# Smart_Tiestu_v4.net
KiCad netlist of a schematic drawn in EasyEDA
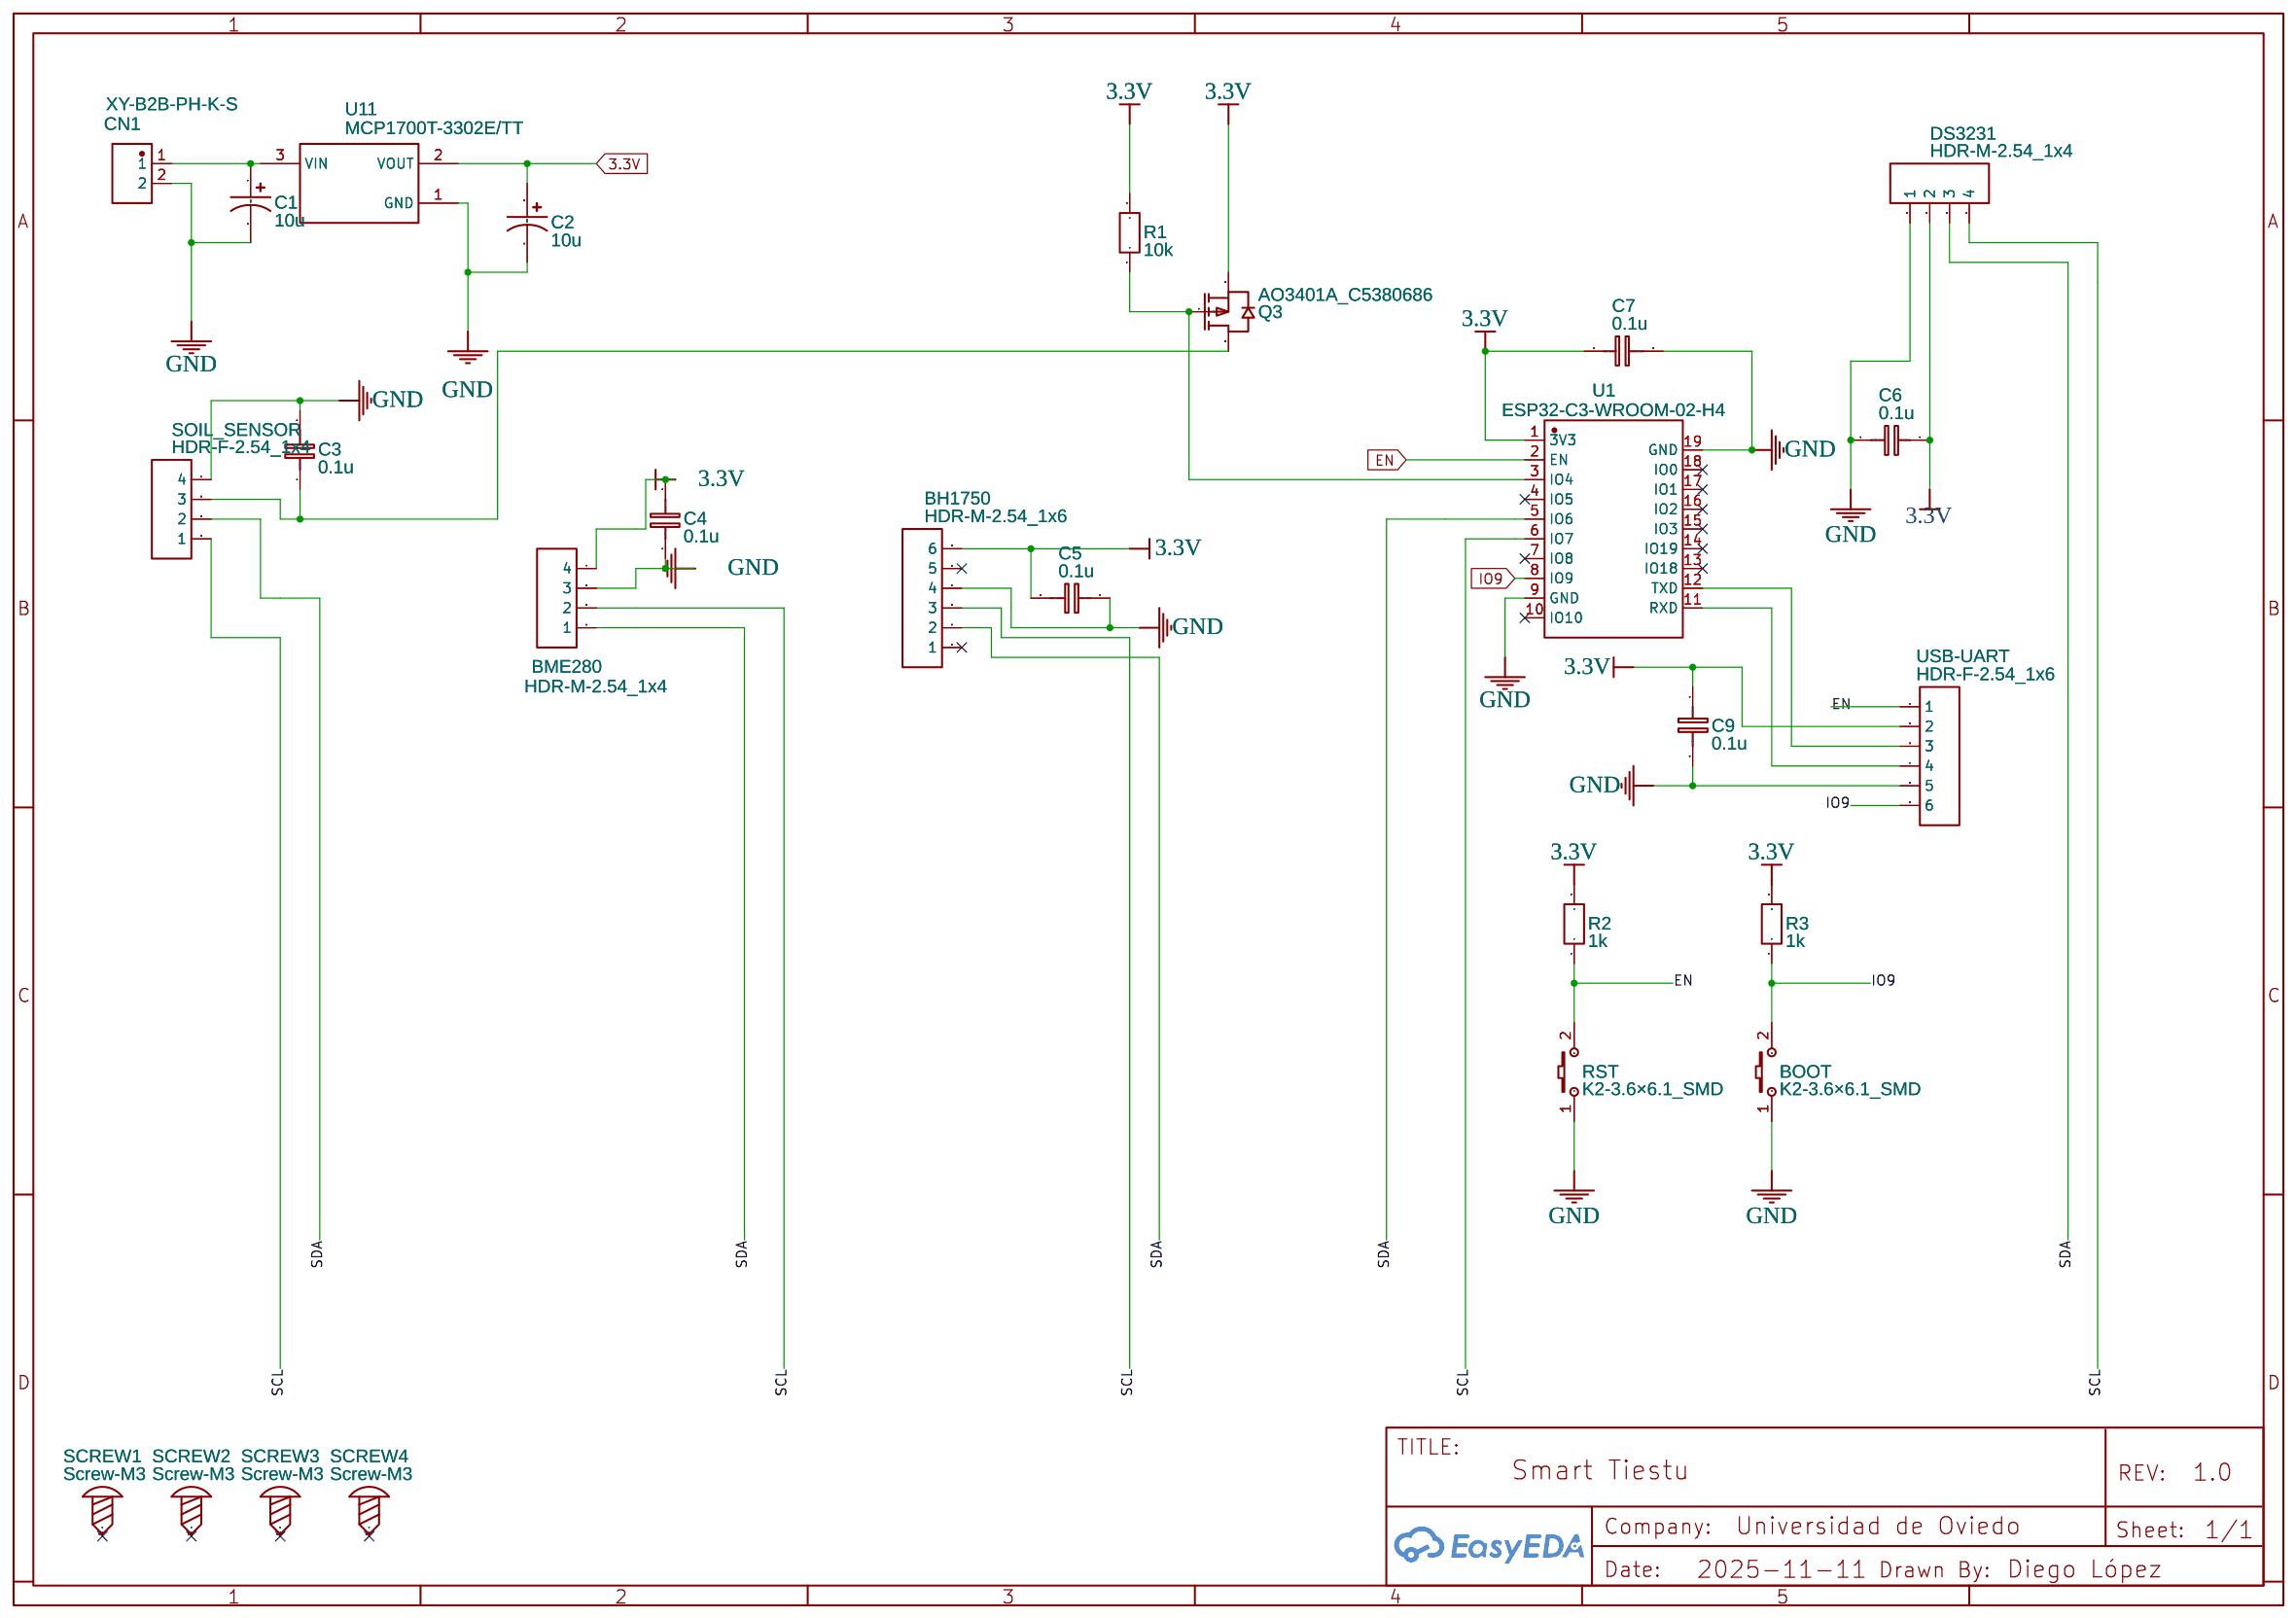
[diagram p0: schematic sheet]

(export (version "E")
  (design (tool "Eeschema 10.0.6"))
  (components
    (comp (ref "BH1750") (value "HDR-M-2.54_1x6") (libsource (lib "") (part "HDR-M-2.54_1x6")))
    (comp (ref "BME280") (value "HDR-M-2.54_1x4") (libsource (lib "") (part "HDR-M-2.54_1x4_1")))
    (comp (ref "BOOT")
      (value "K2-3.6×6.1_SMD")
      (fields (field (name "Manufacturer Part") "K2-1107ST-A4SW-06"))
      (libsource (lib "") (part "K2-3.6×6.1_SMD_1"))
    )
    (comp (ref "C1") (value "10u") (libsource (lib "") (part "C_Tan_SMD_A_US_1")))
    (comp (ref "C2") (value "10u") (libsource (lib "") (part "C_Tan_SMD_A_US")))
    (comp (ref "C3") (value "0.1u") (libsource (lib "") (part "C_0805_EU_1")))
    (comp (ref "C4") (value "0.1u") (libsource (lib "") (part "C_0805_EU_1")))
    (comp (ref "C5") (value "0.1u") (libsource (lib "") (part "C_0805_EU_2")))
    (comp (ref "C6") (value "0.1u") (libsource (lib "") (part "C_0805_EU")))
    (comp (ref "C7") (value "0.1u") (libsource (lib "") (part "C_0805_EU_4")))
    (comp (ref "C9") (value "0.1u") (libsource (lib "") (part "C_0805_EU_3")))
    (comp (ref "CN1")
      (value "XY-B2B-PH-K-S")
      (fields (field (name "Manufacturer") "XYECONN(辛译)"))
      (libsource (lib "") (part "XY-B2B-PH-K-S"))
    )
    (comp (ref "DS3231") (value "HDR-M-2.54_1x4") (libsource (lib "") (part "HDR-M-2.54_1x4")))
    (comp (ref "Q3")
      (value "AO3401A_C5380686")
      (fields (field (name "Manufacturer Part") "AO3401A") (field (name "Manufacturer") "FUXINSEMI(富芯森美)"))
      (libsource (lib "") (part "AO3401A_C5380686"))
    )
    (comp (ref "R1") (value "10k") (libsource (lib "") (part "R_0603_EU")))
    (comp (ref "R2") (value "1k") (libsource (lib "") (part "R_0603_EU")))
    (comp (ref "R3") (value "1k") (libsource (lib "") (part "R_0603_EU")))
    (comp (ref "RST")
      (value "K2-3.6×6.1_SMD")
      (fields (field (name "Manufacturer Part") "K2-1107ST-A4SW-06"))
      (libsource (lib "") (part "K2-3.6×6.1_SMD"))
    )
    (comp (ref "SCREW1") (value "Screw-M3") (libsource (lib "") (part "Screw-M3")))
    (comp (ref "SCREW2") (value "Screw-M3") (libsource (lib "") (part "Screw-M3")))
    (comp (ref "SCREW3") (value "Screw-M3") (libsource (lib "") (part "Screw-M3")))
    (comp (ref "SCREW4") (value "Screw-M3") (libsource (lib "") (part "Screw-M3")))
    (comp (ref "SOIL_SENSOR") (value "HDR-F-2.54_1x4") (libsource (lib "") (part "HDR-F-2.54_1x4")))
    (comp (ref "U1")
      (value "ESP32-C3-WROOM-02-H4")
      (fields (field (name "Manufacturer") "ESPRESSIF(乐鑫)"))
      (libsource (lib "") (part "ESP32-C3-WROOM-02-H4"))
    )
    (comp (ref "U11")
      (value "MCP1700T-3302E/TT")
      (fields (field (name "Manufacturer") "MICROCHIP(美国微芯)"))
      (libsource (lib "") (part "MCP1700T-3302E/TT"))
    )
    (comp (ref "USB-UART") (value "HDR-F-2.54_1x6") (libsource (lib "") (part "HDR-F-2.54_1x6")))
  )
  (nets
    (net (code "1") (name "/SCL") (class "Default")
      (node (ref "BH1750") (pin "3") (pinfunction "3_3") (pintype "input"))
      (node (ref "BME280") (pin "2") (pinfunction "2_2") (pintype "unspecified"))
      (node (ref "DS3231") (pin "4") (pinfunction "4_4") (pintype "unspecified"))
      (node (ref "SOIL_SENSOR") (pin "1") (pinfunction "1_1") (pintype "unspecified"))
      (node (ref "U1") (pin "6") (pinfunction "IO7_6") (pintype "unspecified"))
    )
    (net (code "2") (name "/SDA") (class "Default")
      (node (ref "BH1750") (pin "2") (pinfunction "2_2") (pintype "input"))
      (node (ref "BME280") (pin "1") (pinfunction "1_1") (pintype "unspecified"))
      (node (ref "DS3231") (pin "3") (pinfunction "3_3") (pintype "unspecified"))
      (node (ref "SOIL_SENSOR") (pin "2") (pinfunction "2_2") (pintype "unspecified"))
      (node (ref "U1") (pin "5") (pinfunction "IO6_5") (pintype "unspecified"))
    )
    (net (code "3") (name "3.3V") (class "Default")
      (node (ref "BH1750") (pin "6") (pinfunction "6_6") (pintype "input"))
      (node (ref "BME280") (pin "4") (pinfunction "4_4") (pintype "unspecified"))
      (node (ref "C2") (pin "1") (pinfunction "1_1") (pintype "unspecified"))
      (node (ref "C4") (pin "2") (pinfunction "2_2") (pintype "unspecified"))
      (node (ref "C5") (pin "2") (pinfunction "2_2") (pintype "unspecified"))
      (node (ref "C6") (pin "1") (pinfunction "1_1") (pintype "unspecified"))
      (node (ref "C7") (pin "1") (pinfunction "1_1") (pintype "unspecified"))
      (node (ref "C9") (pin "1") (pinfunction "1_1") (pintype "unspecified"))
      (node (ref "DS3231") (pin "2") (pinfunction "2_2") (pintype "unspecified"))
      (node (ref "Q3") (pin "2") (pinfunction "S_2") (pintype "unspecified"))
      (node (ref "R1") (pin "2") (pinfunction "2_2") (pintype "unspecified"))
      (node (ref "R2") (pin "2") (pinfunction "2_2") (pintype "unspecified"))
      (node (ref "R3") (pin "2") (pinfunction "2_2") (pintype "unspecified"))
      (node (ref "U1") (pin "1") (pinfunction "3V3_1") (pintype "unspecified"))
      (node (ref "U11") (pin "2") (pinfunction "VOUT_2") (pintype "passive"))
      (node (ref "USB-UART") (pin "2") (pinfunction "2_2") (pintype "input"))
    )
    (net (code "4") (name "EN") (class "Default")
      (node (ref "R2") (pin "1") (pinfunction "1_1") (pintype "unspecified"))
      (node (ref "RST") (pin "2") (pinfunction "2_2") (pintype "unspecified"))
      (node (ref "U1") (pin "2") (pinfunction "EN_2") (pintype "unspecified"))
      (node (ref "USB-UART") (pin "1") (pinfunction "1_1") (pintype "input"))
    )
    (net (code "5") (name "GND") (class "Default")
      (node (ref "BH1750") (pin "4") (pinfunction "4_4") (pintype "input"))
      (node (ref "BME280") (pin "3") (pinfunction "3_3") (pintype "unspecified"))
      (node (ref "BOOT") (pin "1") (pinfunction "1_1") (pintype "unspecified"))
      (node (ref "C1") (pin "2") (pinfunction "2_2") (pintype "unspecified"))
      (node (ref "C2") (pin "2") (pinfunction "2_2") (pintype "unspecified"))
      (node (ref "C3") (pin "2") (pinfunction "2_2") (pintype "unspecified"))
      (node (ref "C4") (pin "1") (pinfunction "1_1") (pintype "unspecified"))
      (node (ref "C5") (pin "1") (pinfunction "1_1") (pintype "unspecified"))
      (node (ref "C6") (pin "2") (pinfunction "2_2") (pintype "unspecified"))
      (node (ref "C7") (pin "2") (pinfunction "2_2") (pintype "unspecified"))
      (node (ref "C9") (pin "2") (pinfunction "2_2") (pintype "unspecified"))
      (node (ref "CN1") (pin "2") (pinfunction "2_2") (pintype "unspecified"))
      (node (ref "DS3231") (pin "1") (pinfunction "1_1") (pintype "unspecified"))
      (node (ref "RST") (pin "1") (pinfunction "1_1") (pintype "unspecified"))
      (node (ref "SOIL_SENSOR") (pin "4") (pinfunction "4_4") (pintype "unspecified"))
      (node (ref "U1") (pin "19") (pinfunction "GND_19") (pintype "unspecified"))
      (node (ref "U1") (pin "9") (pinfunction "GND_9") (pintype "unspecified"))
      (node (ref "U11") (pin "1") (pinfunction "GND_1") (pintype "passive"))
      (node (ref "USB-UART") (pin "5") (pinfunction "5_5") (pintype "input"))
    )
    (net (code "6") (name "IO9") (class "Default")
      (node (ref "BOOT") (pin "2") (pinfunction "2_2") (pintype "unspecified"))
      (node (ref "R3") (pin "1") (pinfunction "1_1") (pintype "unspecified"))
      (node (ref "U1") (pin "8") (pinfunction "IO9_8") (pintype "unspecified"))
      (node (ref "USB-UART") (pin "6") (pinfunction "6_6") (pintype "input"))
    )
    (net (code "7") (name "Net-(Q3-D)") (class "Default")
      (node (ref "C3") (pin "1") (pinfunction "1_1") (pintype "unspecified"))
      (node (ref "Q3") (pin "3") (pinfunction "D_3") (pintype "unspecified"))
      (node (ref "SOIL_SENSOR") (pin "3") (pinfunction "3_3") (pintype "unspecified"))
    )
    (net (code "8") (name "Net-(Q3-G)") (class "Default")
      (node (ref "Q3") (pin "1") (pinfunction "G_1") (pintype "unspecified"))
      (node (ref "R1") (pin "1") (pinfunction "1_1") (pintype "unspecified"))
      (node (ref "U1") (pin "3") (pinfunction "IO4_3") (pintype "unspecified"))
    )
    (net (code "9") (name "Net-(U1-RXD)") (class "Default")
      (node (ref "U1") (pin "11") (pinfunction "RXD_11") (pintype "unspecified"))
      (node (ref "USB-UART") (pin "4") (pinfunction "4_4") (pintype "input"))
    )
    (net (code "10") (name "Net-(U1-TXD)") (class "Default")
      (node (ref "U1") (pin "12") (pinfunction "TXD_12") (pintype "unspecified"))
      (node (ref "USB-UART") (pin "3") (pinfunction "3_3") (pintype "input"))
    )
    (net (code "11") (name "Net-(U11-VIN)") (class "Default")
      (node (ref "C1") (pin "1") (pinfunction "1_1") (pintype "unspecified"))
      (node (ref "CN1") (pin "1") (pinfunction "1_1") (pintype "unspecified"))
      (node (ref "U11") (pin "3") (pinfunction "VIN_3") (pintype "passive"))
    )
    (net (code "12") (name "unconnected-(BH1750-Pad1)") (class "Default")
      (node (ref "BH1750") (pin "1") (pinfunction "1_1") (pintype "input+no_connect"))
    )
    (net (code "13") (name "unconnected-(BH1750-Pad5)") (class "Default")
      (node (ref "BH1750") (pin "5") (pinfunction "5_5") (pintype "input+no_connect"))
    )
    (net (code "14") (name "unconnected-(SCREW1-Pad1)") (class "Default")
      (node (ref "SCREW1") (pin "1") (pinfunction "1_1") (pintype "unspecified+no_connect"))
    )
    (net (code "15") (name "unconnected-(SCREW2-Pad1)") (class "Default")
      (node (ref "SCREW2") (pin "1") (pinfunction "1_1") (pintype "unspecified+no_connect"))
    )
    (net (code "16") (name "unconnected-(SCREW3-Pad1)") (class "Default")
      (node (ref "SCREW3") (pin "1") (pinfunction "1_1") (pintype "unspecified+no_connect"))
    )
    (net (code "17") (name "unconnected-(SCREW4-Pad1)") (class "Default")
      (node (ref "SCREW4") (pin "1") (pinfunction "1_1") (pintype "unspecified+no_connect"))
    )
    (net (code "18") (name "unconnected-(U1-IO0-Pad18)") (class "Default")
      (node (ref "U1") (pin "18") (pinfunction "IO0_18") (pintype "unspecified+no_connect"))
    )
    (net (code "19") (name "unconnected-(U1-IO1-Pad17)") (class "Default")
      (node (ref "U1") (pin "17") (pinfunction "IO1_17") (pintype "unspecified+no_connect"))
    )
    (net (code "20") (name "unconnected-(U1-IO2-Pad16)") (class "Default")
      (node (ref "U1") (pin "16") (pinfunction "IO2_16") (pintype "unspecified+no_connect"))
    )
    (net (code "21") (name "unconnected-(U1-IO3-Pad15)") (class "Default")
      (node (ref "U1") (pin "15") (pinfunction "IO3_15") (pintype "unspecified+no_connect"))
    )
    (net (code "22") (name "unconnected-(U1-IO5-Pad4)") (class "Default")
      (node (ref "U1") (pin "4") (pinfunction "IO5_4") (pintype "unspecified+no_connect"))
    )
    (net (code "23") (name "unconnected-(U1-IO8-Pad7)") (class "Default")
      (node (ref "U1") (pin "7") (pinfunction "IO8_7") (pintype "unspecified+no_connect"))
    )
    (net (code "24") (name "unconnected-(U1-IO10-Pad10)") (class "Default")
      (node (ref "U1") (pin "10") (pinfunction "IO10_10") (pintype "unspecified+no_connect"))
    )
    (net (code "25") (name "unconnected-(U1-IO18-Pad13)") (class "Default")
      (node (ref "U1") (pin "13") (pinfunction "IO18_13") (pintype "unspecified+no_connect"))
    )
    (net (code "26") (name "unconnected-(U1-IO19-Pad14)") (class "Default")
      (node (ref "U1") (pin "14") (pinfunction "IO19_14") (pintype "unspecified+no_connect"))
    )
  )
)
